# Switching_circuit.net
KiCad netlist of a schematic drawn in Altium Designer
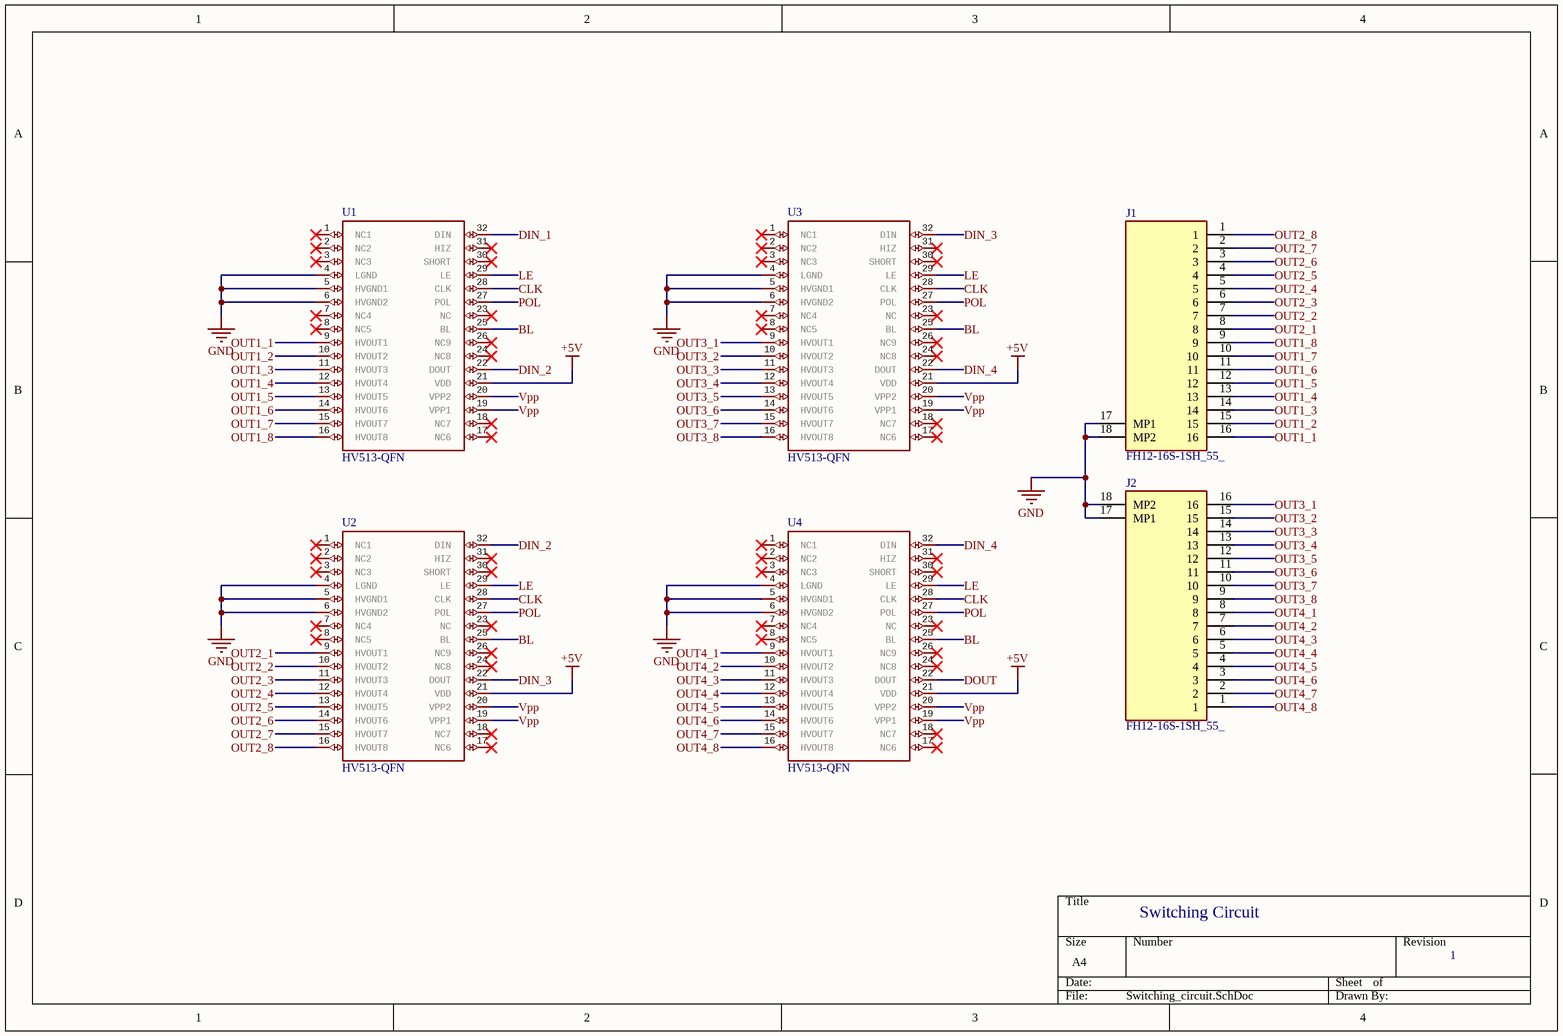
[diagram p0: Switching_circuit.SchDoc]

(export (version "E")
  (design (tool "Eeschema 10.0.6"))
  (components
    (comp (ref "J1")
      (value "FH12-16S-1SH_55_")
      (footprint "SamacSys:FH1216S1SH55")
      (description "Connector")
      (fields
        (field (name "MANUFACTURER_PART_NUMBER") "FH12-16S-1SH(55)")
        (field (name "MOUSER PART NUMBER") "798-FH12-16S-1SH55")
      )
      (libsource (lib "SamacSys") (part "FH12-16S-1SH_55_"))
    )
    (comp (ref "J2")
      (value "FH12-16S-1SH_55_")
      (footprint "SamacSys:FH1216S1SH55")
      (description "Connector")
      (fields
        (field (name "MANUFACTURER_PART_NUMBER") "FH12-16S-1SH(55)")
        (field (name "MOUSER PART NUMBER") "798-FH12-16S-1SH55")
      )
      (libsource (lib "") (part "FH12-16S-1SH_55__1"))
    )
    (comp (ref "U1")
      (value "HV513-QFN")
      (footprint "HV513-QFN")
      (libsource (lib "Switching_Circuit_Components") (part "HV513-QFN"))
    )
    (comp (ref "U2")
      (value "HV513-QFN")
      (footprint "HV513-QFN")
      (libsource (lib "Switching_Circuit_Components") (part "HV513-QFN"))
    )
    (comp (ref "U3")
      (value "HV513-QFN")
      (footprint "HV513-QFN")
      (libsource (lib "Switching_Circuit_Components") (part "HV513-QFN"))
    )
    (comp (ref "U4")
      (value "HV513-QFN")
      (footprint "HV513-QFN")
      (libsource (lib "Switching_Circuit_Components") (part "HV513-QFN"))
    )
  )
  (nets
    (net (code "1") (name "+5V") (class "Default")
      (node (ref "U1") (pin "21") (pinfunction "VDD_21") (pintype "bidirectional"))
      (node (ref "U2") (pin "21") (pinfunction "VDD_21") (pintype "bidirectional"))
      (node (ref "U3") (pin "21") (pinfunction "VDD_21") (pintype "bidirectional"))
      (node (ref "U4") (pin "21") (pinfunction "VDD_21") (pintype "bidirectional"))
    )
    (net (code "2") (name "/BL") (class "Default")
      (node (ref "U1") (pin "25") (pinfunction "BL_25") (pintype "bidirectional"))
      (node (ref "U2") (pin "25") (pinfunction "BL_25") (pintype "bidirectional"))
      (node (ref "U3") (pin "25") (pinfunction "BL_25") (pintype "bidirectional"))
      (node (ref "U4") (pin "25") (pinfunction "BL_25") (pintype "bidirectional"))
    )
    (net (code "3") (name "/CLK") (class "Default")
      (node (ref "U1") (pin "28") (pinfunction "CLK_28") (pintype "bidirectional"))
      (node (ref "U2") (pin "28") (pinfunction "CLK_28") (pintype "bidirectional"))
      (node (ref "U3") (pin "28") (pinfunction "CLK_28") (pintype "bidirectional"))
      (node (ref "U4") (pin "28") (pinfunction "CLK_28") (pintype "bidirectional"))
    )
    (net (code "4") (name "/DIN_1") (class "Default")
      (node (ref "U1") (pin "32") (pinfunction "DIN_32") (pintype "bidirectional"))
    )
    (net (code "5") (name "/DIN_2") (class "Default")
      (node (ref "U1") (pin "22") (pinfunction "DOUT_22") (pintype "bidirectional"))
      (node (ref "U2") (pin "32") (pinfunction "DIN_32") (pintype "bidirectional"))
    )
    (net (code "6") (name "/DIN_3") (class "Default")
      (node (ref "U2") (pin "22") (pinfunction "DOUT_22") (pintype "bidirectional"))
      (node (ref "U3") (pin "32") (pinfunction "DIN_32") (pintype "bidirectional"))
    )
    (net (code "7") (name "/DIN_4") (class "Default")
      (node (ref "U3") (pin "22") (pinfunction "DOUT_22") (pintype "bidirectional"))
      (node (ref "U4") (pin "32") (pinfunction "DIN_32") (pintype "bidirectional"))
    )
    (net (code "8") (name "/DOUT") (class "Default")
      (node (ref "U4") (pin "22") (pinfunction "DOUT_22") (pintype "bidirectional"))
    )
    (net (code "9") (name "/LE") (class "Default")
      (node (ref "U1") (pin "29") (pinfunction "LE_29") (pintype "bidirectional"))
      (node (ref "U2") (pin "29") (pinfunction "LE_29") (pintype "bidirectional"))
      (node (ref "U3") (pin "29") (pinfunction "LE_29") (pintype "bidirectional"))
      (node (ref "U4") (pin "29") (pinfunction "LE_29") (pintype "bidirectional"))
    )
    (net (code "10") (name "/OUT1_1") (class "Default")
      (node (ref "J1") (pin "16") (pinfunction "16_16") (pintype "passive"))
      (node (ref "U1") (pin "9") (pinfunction "HVOUT1_9") (pintype "bidirectional"))
    )
    (net (code "11") (name "/OUT1_2") (class "Default")
      (node (ref "J1") (pin "15") (pinfunction "15_15") (pintype "passive"))
      (node (ref "U1") (pin "10") (pinfunction "HVOUT2_10") (pintype "bidirectional"))
    )
    (net (code "12") (name "/OUT1_3") (class "Default")
      (node (ref "J1") (pin "14") (pinfunction "14_14") (pintype "passive"))
      (node (ref "U1") (pin "11") (pinfunction "HVOUT3_11") (pintype "bidirectional"))
    )
    (net (code "13") (name "/OUT1_4") (class "Default")
      (node (ref "J1") (pin "13") (pinfunction "13_13") (pintype "passive"))
      (node (ref "U1") (pin "12") (pinfunction "HVOUT4_12") (pintype "bidirectional"))
    )
    (net (code "14") (name "/OUT1_5") (class "Default")
      (node (ref "J1") (pin "12") (pinfunction "12_12") (pintype "passive"))
      (node (ref "U1") (pin "13") (pinfunction "HVOUT5_13") (pintype "bidirectional"))
    )
    (net (code "15") (name "/OUT1_6") (class "Default")
      (node (ref "J1") (pin "11") (pinfunction "11_11") (pintype "passive"))
      (node (ref "U1") (pin "14") (pinfunction "HVOUT6_14") (pintype "bidirectional"))
    )
    (net (code "16") (name "/OUT1_7") (class "Default")
      (node (ref "J1") (pin "10") (pinfunction "10_10") (pintype "passive"))
      (node (ref "U1") (pin "15") (pinfunction "HVOUT7_15") (pintype "bidirectional"))
    )
    (net (code "17") (name "/OUT1_8") (class "Default")
      (node (ref "J1") (pin "9") (pinfunction "9_9") (pintype "passive"))
      (node (ref "U1") (pin "16") (pinfunction "HVOUT8_16") (pintype "bidirectional"))
    )
    (net (code "18") (name "/OUT2_1") (class "Default")
      (node (ref "J1") (pin "8") (pinfunction "8_8") (pintype "passive"))
      (node (ref "U2") (pin "9") (pinfunction "HVOUT1_9") (pintype "bidirectional"))
    )
    (net (code "19") (name "/OUT2_2") (class "Default")
      (node (ref "J1") (pin "7") (pinfunction "7_7") (pintype "passive"))
      (node (ref "U2") (pin "10") (pinfunction "HVOUT2_10") (pintype "bidirectional"))
    )
    (net (code "20") (name "/OUT2_3") (class "Default")
      (node (ref "J1") (pin "6") (pinfunction "6_6") (pintype "passive"))
      (node (ref "U2") (pin "11") (pinfunction "HVOUT3_11") (pintype "bidirectional"))
    )
    (net (code "21") (name "/OUT2_4") (class "Default")
      (node (ref "J1") (pin "5") (pinfunction "5_5") (pintype "passive"))
      (node (ref "U2") (pin "12") (pinfunction "HVOUT4_12") (pintype "bidirectional"))
    )
    (net (code "22") (name "/OUT2_5") (class "Default")
      (node (ref "J1") (pin "4") (pinfunction "4_4") (pintype "passive"))
      (node (ref "U2") (pin "13") (pinfunction "HVOUT5_13") (pintype "bidirectional"))
    )
    (net (code "23") (name "/OUT2_6") (class "Default")
      (node (ref "J1") (pin "3") (pinfunction "3_3") (pintype "passive"))
      (node (ref "U2") (pin "14") (pinfunction "HVOUT6_14") (pintype "bidirectional"))
    )
    (net (code "24") (name "/OUT2_7") (class "Default")
      (node (ref "J1") (pin "2") (pinfunction "2_2") (pintype "passive"))
      (node (ref "U2") (pin "15") (pinfunction "HVOUT7_15") (pintype "bidirectional"))
    )
    (net (code "25") (name "/OUT2_8") (class "Default")
      (node (ref "J1") (pin "1") (pinfunction "1_1") (pintype "passive"))
      (node (ref "U2") (pin "16") (pinfunction "HVOUT8_16") (pintype "bidirectional"))
    )
    (net (code "26") (name "/OUT3_1") (class "Default")
      (node (ref "J2") (pin "16") (pinfunction "16_16") (pintype "passive"))
      (node (ref "U3") (pin "9") (pinfunction "HVOUT1_9") (pintype "bidirectional"))
    )
    (net (code "27") (name "/OUT3_2") (class "Default")
      (node (ref "J2") (pin "15") (pinfunction "15_15") (pintype "passive"))
      (node (ref "U3") (pin "10") (pinfunction "HVOUT2_10") (pintype "bidirectional"))
    )
    (net (code "28") (name "/OUT3_3") (class "Default")
      (node (ref "J2") (pin "14") (pinfunction "14_14") (pintype "passive"))
      (node (ref "U3") (pin "11") (pinfunction "HVOUT3_11") (pintype "bidirectional"))
    )
    (net (code "29") (name "/OUT3_4") (class "Default")
      (node (ref "J2") (pin "13") (pinfunction "13_13") (pintype "passive"))
      (node (ref "U3") (pin "12") (pinfunction "HVOUT4_12") (pintype "bidirectional"))
    )
    (net (code "30") (name "/OUT3_5") (class "Default")
      (node (ref "J2") (pin "12") (pinfunction "12_12") (pintype "passive"))
      (node (ref "U3") (pin "13") (pinfunction "HVOUT5_13") (pintype "bidirectional"))
    )
    (net (code "31") (name "/OUT3_6") (class "Default")
      (node (ref "J2") (pin "11") (pinfunction "11_11") (pintype "passive"))
      (node (ref "U3") (pin "14") (pinfunction "HVOUT6_14") (pintype "bidirectional"))
    )
    (net (code "32") (name "/OUT3_7") (class "Default")
      (node (ref "J2") (pin "10") (pinfunction "10_10") (pintype "passive"))
      (node (ref "U3") (pin "15") (pinfunction "HVOUT7_15") (pintype "bidirectional"))
    )
    (net (code "33") (name "/OUT3_8") (class "Default")
      (node (ref "J2") (pin "9") (pinfunction "9_9") (pintype "passive"))
      (node (ref "U3") (pin "16") (pinfunction "HVOUT8_16") (pintype "bidirectional"))
    )
    (net (code "34") (name "/OUT4_1") (class "Default")
      (node (ref "J2") (pin "8") (pinfunction "8_8") (pintype "passive"))
      (node (ref "U4") (pin "9") (pinfunction "HVOUT1_9") (pintype "bidirectional"))
    )
    (net (code "35") (name "/OUT4_2") (class "Default")
      (node (ref "J2") (pin "7") (pinfunction "7_7") (pintype "passive"))
      (node (ref "U4") (pin "10") (pinfunction "HVOUT2_10") (pintype "bidirectional"))
    )
    (net (code "36") (name "/OUT4_3") (class "Default")
      (node (ref "J2") (pin "6") (pinfunction "6_6") (pintype "passive"))
      (node (ref "U4") (pin "11") (pinfunction "HVOUT3_11") (pintype "bidirectional"))
    )
    (net (code "37") (name "/OUT4_4") (class "Default")
      (node (ref "J2") (pin "5") (pinfunction "5_5") (pintype "passive"))
      (node (ref "U4") (pin "12") (pinfunction "HVOUT4_12") (pintype "bidirectional"))
    )
    (net (code "38") (name "/OUT4_5") (class "Default")
      (node (ref "J2") (pin "4") (pinfunction "4_4") (pintype "passive"))
      (node (ref "U4") (pin "13") (pinfunction "HVOUT5_13") (pintype "bidirectional"))
    )
    (net (code "39") (name "/OUT4_6") (class "Default")
      (node (ref "J2") (pin "3") (pinfunction "3_3") (pintype "passive"))
      (node (ref "U4") (pin "14") (pinfunction "HVOUT6_14") (pintype "bidirectional"))
    )
    (net (code "40") (name "/OUT4_7") (class "Default")
      (node (ref "J2") (pin "2") (pinfunction "2_2") (pintype "passive"))
      (node (ref "U4") (pin "15") (pinfunction "HVOUT7_15") (pintype "bidirectional"))
    )
    (net (code "41") (name "/OUT4_8") (class "Default")
      (node (ref "J2") (pin "1") (pinfunction "1_1") (pintype "passive"))
      (node (ref "U4") (pin "16") (pinfunction "HVOUT8_16") (pintype "bidirectional"))
    )
    (net (code "42") (name "/POL") (class "Default")
      (node (ref "U1") (pin "27") (pinfunction "POL_27") (pintype "bidirectional"))
      (node (ref "U2") (pin "27") (pinfunction "POL_27") (pintype "bidirectional"))
      (node (ref "U3") (pin "27") (pinfunction "POL_27") (pintype "bidirectional"))
      (node (ref "U4") (pin "27") (pinfunction "POL_27") (pintype "bidirectional"))
    )
    (net (code "43") (name "/Vpp") (class "Default")
      (node (ref "U1") (pin "19") (pinfunction "VPP1_19") (pintype "bidirectional"))
      (node (ref "U1") (pin "20") (pinfunction "VPP2_20") (pintype "bidirectional"))
      (node (ref "U2") (pin "19") (pinfunction "VPP1_19") (pintype "bidirectional"))
      (node (ref "U2") (pin "20") (pinfunction "VPP2_20") (pintype "bidirectional"))
      (node (ref "U3") (pin "19") (pinfunction "VPP1_19") (pintype "bidirectional"))
      (node (ref "U3") (pin "20") (pinfunction "VPP2_20") (pintype "bidirectional"))
      (node (ref "U4") (pin "19") (pinfunction "VPP1_19") (pintype "bidirectional"))
      (node (ref "U4") (pin "20") (pinfunction "VPP2_20") (pintype "bidirectional"))
    )
    (net (code "44") (name "GND") (class "Default")
      (node (ref "J1") (pin "17") (pinfunction "MP1_17") (pintype "passive"))
      (node (ref "J1") (pin "18") (pinfunction "MP2_18") (pintype "passive"))
      (node (ref "J2") (pin "17") (pinfunction "MP1_17") (pintype "passive"))
      (node (ref "J2") (pin "18") (pinfunction "MP2_18") (pintype "passive"))
      (node (ref "U1") (pin "4") (pinfunction "LGND_4") (pintype "bidirectional"))
      (node (ref "U1") (pin "5") (pinfunction "HVGND1_5") (pintype "bidirectional"))
      (node (ref "U1") (pin "6") (pinfunction "HVGND2_6") (pintype "bidirectional"))
      (node (ref "U2") (pin "4") (pinfunction "LGND_4") (pintype "bidirectional"))
      (node (ref "U2") (pin "5") (pinfunction "HVGND1_5") (pintype "bidirectional"))
      (node (ref "U2") (pin "6") (pinfunction "HVGND2_6") (pintype "bidirectional"))
      (node (ref "U3") (pin "4") (pinfunction "LGND_4") (pintype "bidirectional"))
      (node (ref "U3") (pin "5") (pinfunction "HVGND1_5") (pintype "bidirectional"))
      (node (ref "U3") (pin "6") (pinfunction "HVGND2_6") (pintype "bidirectional"))
      (node (ref "U4") (pin "4") (pinfunction "LGND_4") (pintype "bidirectional"))
      (node (ref "U4") (pin "5") (pinfunction "HVGND1_5") (pintype "bidirectional"))
      (node (ref "U4") (pin "6") (pinfunction "HVGND2_6") (pintype "bidirectional"))
    )
    (net (code "45") (name "unconnected-(U1-HIZ-Pad31)") (class "Default")
      (node (ref "U1") (pin "31") (pinfunction "HIZ_31") (pintype "bidirectional+no_connect"))
    )
    (net (code "46") (name "unconnected-(U1-NC-Pad23)") (class "Default")
      (node (ref "U1") (pin "23") (pinfunction "NC_23") (pintype "bidirectional+no_connect"))
    )
    (net (code "47") (name "unconnected-(U1-NC1-Pad1)") (class "Default")
      (node (ref "U1") (pin "1") (pinfunction "NC1_1") (pintype "bidirectional+no_connect"))
    )
    (net (code "48") (name "unconnected-(U1-NC2-Pad2)") (class "Default")
      (node (ref "U1") (pin "2") (pinfunction "NC2_2") (pintype "bidirectional+no_connect"))
    )
    (net (code "49") (name "unconnected-(U1-NC3-Pad3)") (class "Default")
      (node (ref "U1") (pin "3") (pinfunction "NC3_3") (pintype "bidirectional+no_connect"))
    )
    (net (code "50") (name "unconnected-(U1-NC4-Pad7)") (class "Default")
      (node (ref "U1") (pin "7") (pinfunction "NC4_7") (pintype "bidirectional+no_connect"))
    )
    (net (code "51") (name "unconnected-(U1-NC5-Pad8)") (class "Default")
      (node (ref "U1") (pin "8") (pinfunction "NC5_8") (pintype "bidirectional+no_connect"))
    )
    (net (code "52") (name "unconnected-(U1-NC6-Pad17)") (class "Default")
      (node (ref "U1") (pin "17") (pinfunction "NC6_17") (pintype "bidirectional+no_connect"))
    )
    (net (code "53") (name "unconnected-(U1-NC7-Pad18)") (class "Default")
      (node (ref "U1") (pin "18") (pinfunction "NC7_18") (pintype "bidirectional+no_connect"))
    )
    (net (code "54") (name "unconnected-(U1-NC8-Pad24)") (class "Default")
      (node (ref "U1") (pin "24") (pinfunction "NC8_24") (pintype "bidirectional+no_connect"))
    )
    (net (code "55") (name "unconnected-(U1-NC9-Pad26)") (class "Default")
      (node (ref "U1") (pin "26") (pinfunction "NC9_26") (pintype "bidirectional+no_connect"))
    )
    (net (code "56") (name "unconnected-(U1-SHORT-Pad30)") (class "Default")
      (node (ref "U1") (pin "30") (pinfunction "SHORT_30") (pintype "bidirectional+no_connect"))
    )
    (net (code "57") (name "unconnected-(U2-HIZ-Pad31)") (class "Default")
      (node (ref "U2") (pin "31") (pinfunction "HIZ_31") (pintype "bidirectional+no_connect"))
    )
    (net (code "58") (name "unconnected-(U2-NC-Pad23)") (class "Default")
      (node (ref "U2") (pin "23") (pinfunction "NC_23") (pintype "bidirectional+no_connect"))
    )
    (net (code "59") (name "unconnected-(U2-NC1-Pad1)") (class "Default")
      (node (ref "U2") (pin "1") (pinfunction "NC1_1") (pintype "bidirectional+no_connect"))
    )
    (net (code "60") (name "unconnected-(U2-NC2-Pad2)") (class "Default")
      (node (ref "U2") (pin "2") (pinfunction "NC2_2") (pintype "bidirectional+no_connect"))
    )
    (net (code "61") (name "unconnected-(U2-NC3-Pad3)") (class "Default")
      (node (ref "U2") (pin "3") (pinfunction "NC3_3") (pintype "bidirectional+no_connect"))
    )
    (net (code "62") (name "unconnected-(U2-NC4-Pad7)") (class "Default")
      (node (ref "U2") (pin "7") (pinfunction "NC4_7") (pintype "bidirectional+no_connect"))
    )
    (net (code "63") (name "unconnected-(U2-NC5-Pad8)") (class "Default")
      (node (ref "U2") (pin "8") (pinfunction "NC5_8") (pintype "bidirectional+no_connect"))
    )
    (net (code "64") (name "unconnected-(U2-NC6-Pad17)") (class "Default")
      (node (ref "U2") (pin "17") (pinfunction "NC6_17") (pintype "bidirectional+no_connect"))
    )
    (net (code "65") (name "unconnected-(U2-NC7-Pad18)") (class "Default")
      (node (ref "U2") (pin "18") (pinfunction "NC7_18") (pintype "bidirectional+no_connect"))
    )
    (net (code "66") (name "unconnected-(U2-NC8-Pad24)") (class "Default")
      (node (ref "U2") (pin "24") (pinfunction "NC8_24") (pintype "bidirectional+no_connect"))
    )
    (net (code "67") (name "unconnected-(U2-NC9-Pad26)") (class "Default")
      (node (ref "U2") (pin "26") (pinfunction "NC9_26") (pintype "bidirectional+no_connect"))
    )
    (net (code "68") (name "unconnected-(U2-SHORT-Pad30)") (class "Default")
      (node (ref "U2") (pin "30") (pinfunction "SHORT_30") (pintype "bidirectional+no_connect"))
    )
    (net (code "69") (name "unconnected-(U3-HIZ-Pad31)") (class "Default")
      (node (ref "U3") (pin "31") (pinfunction "HIZ_31") (pintype "bidirectional+no_connect"))
    )
    (net (code "70") (name "unconnected-(U3-NC-Pad23)") (class "Default")
      (node (ref "U3") (pin "23") (pinfunction "NC_23") (pintype "bidirectional+no_connect"))
    )
    (net (code "71") (name "unconnected-(U3-NC1-Pad1)") (class "Default")
      (node (ref "U3") (pin "1") (pinfunction "NC1_1") (pintype "bidirectional+no_connect"))
    )
    (net (code "72") (name "unconnected-(U3-NC2-Pad2)") (class "Default")
      (node (ref "U3") (pin "2") (pinfunction "NC2_2") (pintype "bidirectional+no_connect"))
    )
    (net (code "73") (name "unconnected-(U3-NC3-Pad3)") (class "Default")
      (node (ref "U3") (pin "3") (pinfunction "NC3_3") (pintype "bidirectional+no_connect"))
    )
    (net (code "74") (name "unconnected-(U3-NC4-Pad7)") (class "Default")
      (node (ref "U3") (pin "7") (pinfunction "NC4_7") (pintype "bidirectional+no_connect"))
    )
    (net (code "75") (name "unconnected-(U3-NC5-Pad8)") (class "Default")
      (node (ref "U3") (pin "8") (pinfunction "NC5_8") (pintype "bidirectional+no_connect"))
    )
    (net (code "76") (name "unconnected-(U3-NC6-Pad17)") (class "Default")
      (node (ref "U3") (pin "17") (pinfunction "NC6_17") (pintype "bidirectional+no_connect"))
    )
    (net (code "77") (name "unconnected-(U3-NC7-Pad18)") (class "Default")
      (node (ref "U3") (pin "18") (pinfunction "NC7_18") (pintype "bidirectional+no_connect"))
    )
    (net (code "78") (name "unconnected-(U3-NC8-Pad24)") (class "Default")
      (node (ref "U3") (pin "24") (pinfunction "NC8_24") (pintype "bidirectional+no_connect"))
    )
    (net (code "79") (name "unconnected-(U3-NC9-Pad26)") (class "Default")
      (node (ref "U3") (pin "26") (pinfunction "NC9_26") (pintype "bidirectional+no_connect"))
    )
    (net (code "80") (name "unconnected-(U3-SHORT-Pad30)") (class "Default")
      (node (ref "U3") (pin "30") (pinfunction "SHORT_30") (pintype "bidirectional+no_connect"))
    )
    (net (code "81") (name "unconnected-(U4-HIZ-Pad31)") (class "Default")
      (node (ref "U4") (pin "31") (pinfunction "HIZ_31") (pintype "bidirectional+no_connect"))
    )
    (net (code "82") (name "unconnected-(U4-NC-Pad23)") (class "Default")
      (node (ref "U4") (pin "23") (pinfunction "NC_23") (pintype "bidirectional+no_connect"))
    )
    (net (code "83") (name "unconnected-(U4-NC1-Pad1)") (class "Default")
      (node (ref "U4") (pin "1") (pinfunction "NC1_1") (pintype "bidirectional+no_connect"))
    )
    (net (code "84") (name "unconnected-(U4-NC2-Pad2)") (class "Default")
      (node (ref "U4") (pin "2") (pinfunction "NC2_2") (pintype "bidirectional+no_connect"))
    )
    (net (code "85") (name "unconnected-(U4-NC3-Pad3)") (class "Default")
      (node (ref "U4") (pin "3") (pinfunction "NC3_3") (pintype "bidirectional+no_connect"))
    )
    (net (code "86") (name "unconnected-(U4-NC4-Pad7)") (class "Default")
      (node (ref "U4") (pin "7") (pinfunction "NC4_7") (pintype "bidirectional+no_connect"))
    )
    (net (code "87") (name "unconnected-(U4-NC5-Pad8)") (class "Default")
      (node (ref "U4") (pin "8") (pinfunction "NC5_8") (pintype "bidirectional+no_connect"))
    )
    (net (code "88") (name "unconnected-(U4-NC6-Pad17)") (class "Default")
      (node (ref "U4") (pin "17") (pinfunction "NC6_17") (pintype "bidirectional+no_connect"))
    )
    (net (code "89") (name "unconnected-(U4-NC7-Pad18)") (class "Default")
      (node (ref "U4") (pin "18") (pinfunction "NC7_18") (pintype "bidirectional+no_connect"))
    )
    (net (code "90") (name "unconnected-(U4-NC8-Pad24)") (class "Default")
      (node (ref "U4") (pin "24") (pinfunction "NC8_24") (pintype "bidirectional+no_connect"))
    )
    (net (code "91") (name "unconnected-(U4-NC9-Pad26)") (class "Default")
      (node (ref "U4") (pin "26") (pinfunction "NC9_26") (pintype "bidirectional+no_connect"))
    )
    (net (code "92") (name "unconnected-(U4-SHORT-Pad30)") (class "Default")
      (node (ref "U4") (pin "30") (pinfunction "SHORT_30") (pintype "bidirectional+no_connect"))
    )
  )
)
